# AnalogInputs.net
KiCad netlist of a schematic drawn in Altium Designer
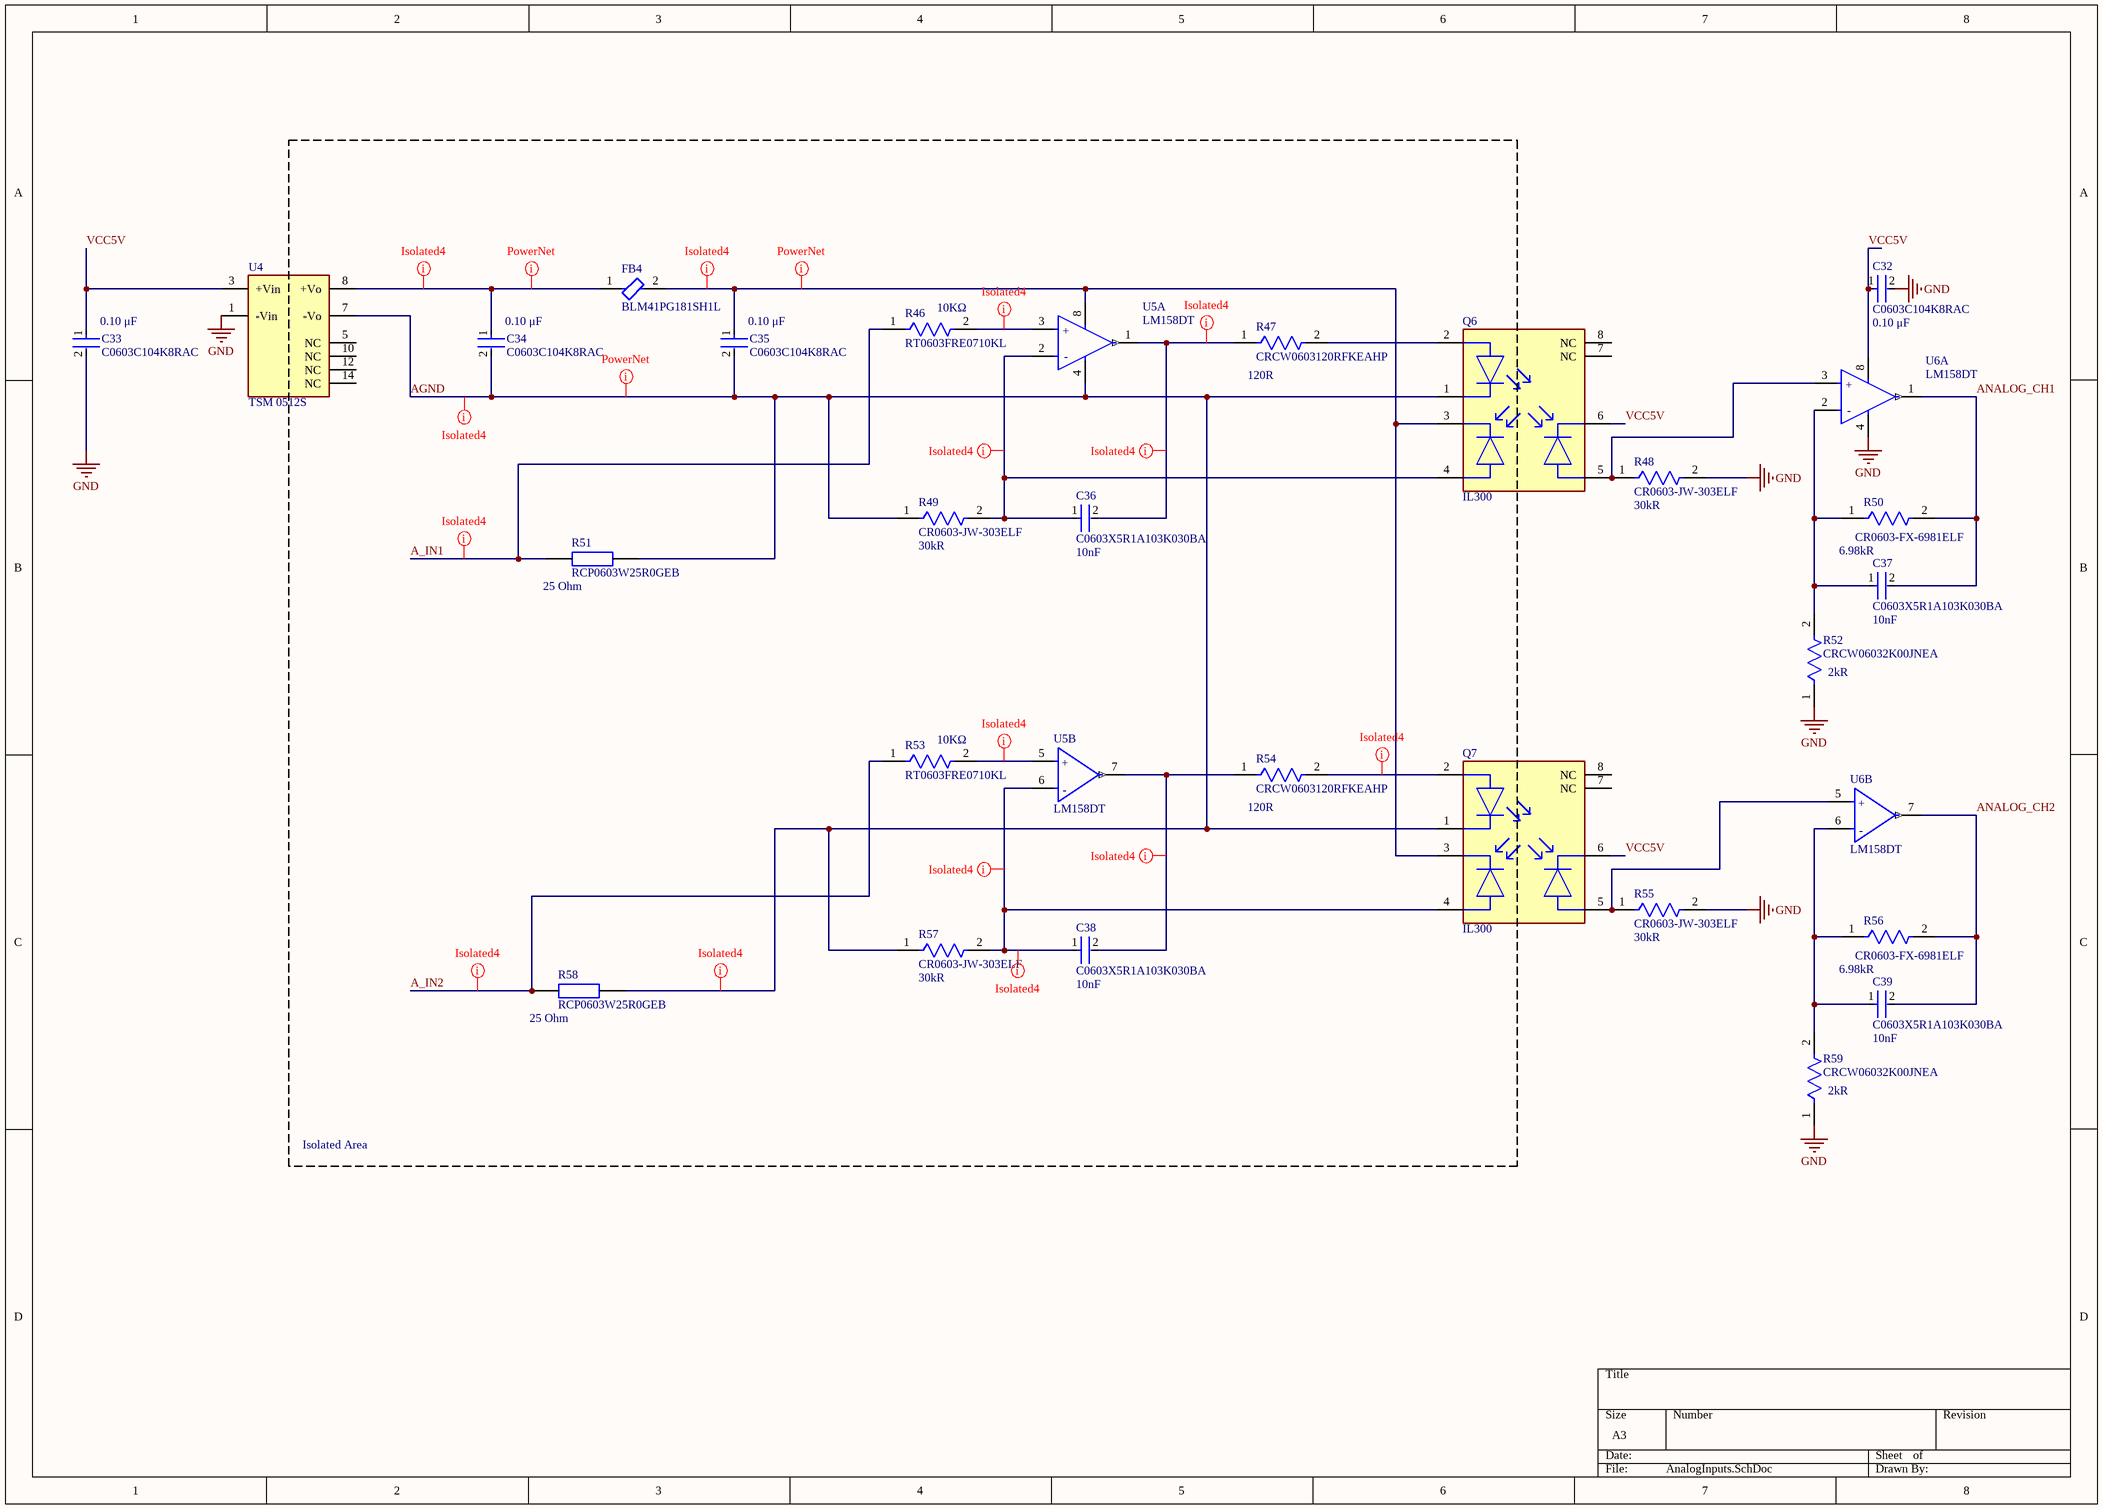
[diagram p0: AnalogInputs.SchDoc]

(export (version "E")
  (design (tool "Eeschema 10.0.6"))
  (components
    (comp (ref "C32")
      (value "C0603C104K8RAC")
      (footprint "FP-C0603C-CF-MFG")
      (description "C0603 0.10 μF X7R 30ppm/°C 10.00% 10 V")
      (fields
        (field (name "MANUFACTURER") "KEMET")
        (field (name "CAPACITANCE") "0.10 μF")
        (field (name "OCTOPART") "https://octopart.com/c0603c104k8rac-kemet-1325403")
      )
      (libsource (lib "Altium Content Vault") (part "b4654b650e69147ec39a6b967a45e02"))
    )
    (comp (ref "C33")
      (value "C0603C104K8RAC")
      (footprint "FP-C0603C-CF-MFG")
      (description "C0603 0.10 μF X7R 30ppm/°C 10.00% 10 V")
      (fields
        (field (name "MANUFACTURER") "KEMET")
        (field (name "CAPACITANCE") "0.10 μF")
        (field (name "OCTOPART") "https://octopart.com/c0603c104k8rac-kemet-1325403")
      )
      (libsource (lib "Altium Content Vault") (part "b4654b650e69147ec39a6b967a45e02"))
    )
    (comp (ref "C34")
      (value "C0603C104K8RAC")
      (footprint "FP-C0603C-CF-MFG")
      (description "C0603 0.10 μF X7R 30ppm/°C 10.00% 10 V")
      (fields
        (field (name "MANUFACTURER") "KEMET")
        (field (name "CAPACITANCE") "0.10 μF")
        (field (name "OCTOPART") "https://octopart.com/c0603c104k8rac-kemet-1325403")
      )
      (libsource (lib "Altium Content Vault") (part "b4654b650e69147ec39a6b967a45e02"))
    )
    (comp (ref "C35")
      (value "C0603C104K8RAC")
      (footprint "FP-C0603C-CF-MFG")
      (description "C0603 0.10 μF X7R 30ppm/°C 10.00% 10 V")
      (fields
        (field (name "MANUFACTURER") "KEMET")
        (field (name "CAPACITANCE") "0.10 μF")
        (field (name "OCTOPART") "https://octopart.com/c0603c104k8rac-kemet-1325403")
      )
      (libsource (lib "Altium Content Vault") (part "b4654b650e69147ec39a6b967a45e02"))
    )
    (comp (ref "C36")
      (value "C0603X5R1A103K030BA")
      (footprint "FP-C0603-030-0_03-MFG")
      (description "Multilayer Ceramic Capacitors 10nF ±10% 10V X5R SMD 0201")
      (fields
        (field (name "CAPACITANCE") "10nF")
        (field (name "TOLERANCE") "10%")
        (field (name "VOLTAGE") "10V")
      )
      (libsource (lib "Altium Content Vault") (part "02cd4be3c70576c341d710602a673aa"))
    )
    (comp (ref "C37")
      (value "C0603X5R1A103K030BA")
      (footprint "FP-C0603-030-0_03-MFG")
      (description "Multilayer Ceramic Capacitors 10nF ±10% 10V X5R SMD 0201")
      (fields
        (field (name "CAPACITANCE") "10nF")
        (field (name "TOLERANCE") "10%")
        (field (name "VOLTAGE") "10V")
      )
      (libsource (lib "Altium Content Vault") (part "02cd4be3c70576c341d710602a673aa"))
    )
    (comp (ref "C38")
      (value "C0603X5R1A103K030BA")
      (footprint "FP-C0603-030-0_03-MFG")
      (description "Multilayer Ceramic Capacitors 10nF ±10% 10V X5R SMD 0201")
      (fields
        (field (name "CAPACITANCE") "10nF")
        (field (name "TOLERANCE") "10%")
        (field (name "VOLTAGE") "10V")
      )
      (libsource (lib "Altium Content Vault") (part "02cd4be3c70576c341d710602a673aa"))
    )
    (comp (ref "C39")
      (value "C0603X5R1A103K030BA")
      (footprint "FP-C0603-030-0_03-MFG")
      (description "Multilayer Ceramic Capacitors 10nF ±10% 10V X5R SMD 0201")
      (fields
        (field (name "CAPACITANCE") "10nF")
        (field (name "TOLERANCE") "10%")
        (field (name "VOLTAGE") "10V")
      )
      (libsource (lib "Altium Content Vault") (part "02cd4be3c70576c341d710602a673aa"))
    )
    (comp (ref "FB4")
      (value "BLM41PG181SH1L")
      (footprint "FP-BLM41-0_2-a1_2-MFG")
      (description "Ferrite Bead, 1806, 180Ω @ 100MHz, 25%, 0.02Ω, 3.5A")
      (fields (field (name "TOLERANCE") "25%"))
      (libsource (lib "Altium Content Vault") (part "5f30dd21d616792df468990f7003faa"))
    )
    (comp (ref "Q6")
      (value "IL300")
      (footprint "FP-83265-MFG")
      (description "OPTOISO 5.3KV LINEAR PHVOLT 8DIP")
      (fields
        (field (name "OCTOPART") "https://octopart.com/il300-vishay-39692656")
        (field (name "MANUFACTURER") "Vishay")
      )
      (libsource (lib "Altium Content Vault") (part "7713484bad07440a39ee692e26a889a"))
    )
    (comp (ref "Q7")
      (value "IL300")
      (footprint "FP-83265-MFG")
      (description "OPTOISO 5.3KV LINEAR PHVOLT 8DIP")
      (fields
        (field (name "OCTOPART") "https://octopart.com/il300-vishay-39692656")
        (field (name "MANUFACTURER") "Vishay")
      )
      (libsource (lib "Altium Content Vault") (part "7713484bad07440a39ee692e26a889a"))
    )
    (comp (ref "R46")
      (value "RT0603FRE0710KL")
      (footprint "FP-RT0603-MFG")
      (description "RES SMD 10K OHM 1% 1/10W 0603")
      (fields
        (field (name "ALTIUM_VALUE") "10KΩ")
        (field (name "MANUFACTURER") "Yageo")
        (field (name "OCTOPART") "https://octopart.com/rt0603fre0710kl-yageo-40009243")
      )
      (libsource (lib "Altium Content Vault") (part "1029c3af85768c4190bb7ad29bc67b5"))
    )
    (comp (ref "R47")
      (value "CRCW0603120RFKEAHP")
      (footprint "FP-CRCW0603-HPe3-MFG")
      (description "RES Thick Film, 120Ω, 1%, 0.33W, 100ppm/°C, 0603")
      (fields (field (name "RESISTANCE") "120R") (field (name "TOLERANCE") "1%"))
      (libsource (lib "Altium Content Vault") (part "1029c3af85768c4190bb7ad29bc67b5"))
    )
    (comp (ref "R48")
      (value "CR0603-JW-303ELF")
      (footprint "FP-CR0603-MFG")
      (description "Thick Film Chip Resistors 0603 30kΩ 0.1W 5% 200ppm/°C")
      (fields (field (name "TOLERANCE") "5%") (field (name "RESISTANCE") "30kR"))
      (libsource (lib "Altium Content Vault") (part "1029c3af85768c4190bb7ad29bc67b5"))
    )
    (comp (ref "R49")
      (value "CR0603-JW-303ELF")
      (footprint "FP-CR0603-MFG")
      (description "Thick Film Chip Resistors 0603 30kΩ 0.1W 5% 200ppm/°C")
      (fields (field (name "TOLERANCE") "5%") (field (name "RESISTANCE") "30kR"))
      (libsource (lib "Altium Content Vault") (part "1029c3af85768c4190bb7ad29bc67b5"))
    )
    (comp (ref "R50")
      (value "CR0603-FX-6981ELF")
      (footprint "FP-CR0603-IPC_B")
      (description "Thick Film Chip Resistors 0603 6.98kΩ 0.1W 1% 100ppm/°C")
      (fields (field (name "RESISTANCE") "6.98kR") (field (name "TOLERANCE") "1%"))
      (libsource (lib "Altium Content Vault") (part "1029c3af85768c4190bb7ad29bc67b5"))
    )
    (comp (ref "R51")
      (value "RCP0603W25R0GEB")
      (footprint "RESC1608X59N")
      (description "Vishay 25 0603 (1608M) Thick Film SMD Resistor +/-2% 1.5W - RCP0603W25R0GEB")
      (fields (field (name "RESISTANCE") "25 Ohm"))
      (libsource (lib "Schlib2") (part "RCP0603W25R0GEB"))
    )
    (comp (ref "R52")
      (value "CRCW06032K00JNEA")
      (footprint "FP-CRCW0603-e3-MFG")
      (description "RES Thick Film, 2kΩ, 5%, 0.1W, 200ppm/°C, 0603")
      (fields (field (name "TOLERANCE") "5%") (field (name "RESISTANCE") "2kR"))
      (libsource (lib "Altium Content Vault") (part "1029c3af85768c4190bb7ad29bc67b5"))
    )
    (comp (ref "R53")
      (value "RT0603FRE0710KL")
      (footprint "FP-RT0603-MFG")
      (description "RES SMD 10K OHM 1% 1/10W 0603")
      (fields
        (field (name "ALTIUM_VALUE") "10KΩ")
        (field (name "MANUFACTURER") "Yageo")
        (field (name "OCTOPART") "https://octopart.com/rt0603fre0710kl-yageo-40009243")
      )
      (libsource (lib "Altium Content Vault") (part "1029c3af85768c4190bb7ad29bc67b5"))
    )
    (comp (ref "R54")
      (value "CRCW0603120RFKEAHP")
      (footprint "FP-CRCW0603-HPe3-MFG")
      (description "RES Thick Film, 120Ω, 1%, 0.33W, 100ppm/°C, 0603")
      (fields (field (name "RESISTANCE") "120R") (field (name "TOLERANCE") "1%"))
      (libsource (lib "Altium Content Vault") (part "1029c3af85768c4190bb7ad29bc67b5"))
    )
    (comp (ref "R55")
      (value "CR0603-JW-303ELF")
      (footprint "FP-CR0603-MFG")
      (description "Thick Film Chip Resistors 0603 30kΩ 0.1W 5% 200ppm/°C")
      (fields (field (name "TOLERANCE") "5%") (field (name "RESISTANCE") "30kR"))
      (libsource (lib "Altium Content Vault") (part "1029c3af85768c4190bb7ad29bc67b5"))
    )
    (comp (ref "R56")
      (value "CR0603-FX-6981ELF")
      (footprint "FP-CR0603-IPC_B")
      (description "Thick Film Chip Resistors 0603 6.98kΩ 0.1W 1% 100ppm/°C")
      (fields (field (name "RESISTANCE") "6.98kR") (field (name "TOLERANCE") "1%"))
      (libsource (lib "Altium Content Vault") (part "1029c3af85768c4190bb7ad29bc67b5"))
    )
    (comp (ref "R57")
      (value "CR0603-JW-303ELF")
      (footprint "FP-CR0603-MFG")
      (description "Thick Film Chip Resistors 0603 30kΩ 0.1W 5% 200ppm/°C")
      (fields (field (name "TOLERANCE") "5%") (field (name "RESISTANCE") "30kR"))
      (libsource (lib "Altium Content Vault") (part "1029c3af85768c4190bb7ad29bc67b5"))
    )
    (comp (ref "R58")
      (value "RCP0603W25R0GEB")
      (footprint "RESC1608X59N")
      (description "Vishay 25 0603 (1608M) Thick Film SMD Resistor +/-2% 1.5W - RCP0603W25R0GEB")
      (fields (field (name "RESISTANCE") "25 Ohm"))
      (libsource (lib "Schlib2") (part "RCP0603W25R0GEB"))
    )
    (comp (ref "R59")
      (value "CRCW06032K00JNEA")
      (footprint "FP-CRCW0603-e3-MFG")
      (description "RES Thick Film, 2kΩ, 5%, 0.1W, 200ppm/°C, 0603")
      (fields (field (name "TOLERANCE") "5%") (field (name "RESISTANCE") "2kR"))
      (libsource (lib "Altium Content Vault") (part "1029c3af85768c4190bb7ad29bc67b5"))
    )
    (comp (ref "U4")
      (value "TSM 0512S")
      (footprint "FP-TSM_0512S-MFG")
      (description "DC DC CONVERTER 12V 960MW")
      (fields
        (field (name "OCTOPART") "https://octopart.com/tsm+0512s-tracopower-7394392")
        (field (name "MANUFACTURER") "Tracopower")
      )
      (libsource (lib "Altium Content Vault") (part "eabb76d147af65372c0c780fc4b7452"))
    )
    (comp (ref "U5")
      (value "LM158DT")
      (footprint "FP-SO8-IPC_C")
      (description "IC OPAMP GP 2 CIRCUIT 8SO")
      (fields
        (field (name "MANUFACTURER") "STMicroelectronics")
        (field (name "OCTOPART") "https://octopart.com/lm158dt-stmicroelectronics-11026426")
      )
      (libsource (lib "Altium Content Vault") (part "5d7e14b575c37a4dd5fc6126976b1ba"))
    )
    (comp (ref "U6")
      (value "LM158DT")
      (footprint "FP-SO8-IPC_C")
      (description "IC OPAMP GP 2 CIRCUIT 8SO")
      (fields
        (field (name "MANUFACTURER") "STMicroelectronics")
        (field (name "OCTOPART") "https://octopart.com/lm158dt-stmicroelectronics-11026426")
      )
      (libsource (lib "Altium Content Vault") (part "5d7e14b575c37a4dd5fc6126976b1ba"))
    )
  )
  (nets
    (net (code "1") (name "/AGND") (class "Default")
      (node (ref "C34") (pin "2") (pinfunction "2_2") (pintype "passive"))
      (node (ref "C35") (pin "2") (pinfunction "2_2") (pintype "passive"))
      (node (ref "Q6") (pin "1") (pinfunction "1_CATHODE_1") (pintype "passive"))
      (node (ref "Q7") (pin "1") (pinfunction "1_CATHODE_1") (pintype "passive"))
      (node (ref "R49") (pin "1") (pinfunction "1_1") (pintype "passive"))
      (node (ref "R51") (pin "2") (pinfunction "2_2") (pintype "passive"))
      (node (ref "R57") (pin "1") (pinfunction "1_1") (pintype "passive"))
      (node (ref "R58") (pin "2") (pinfunction "2_2") (pintype "passive"))
      (node (ref "U4") (pin "7") (pinfunction "-Vo_7") (pintype "power_in"))
      (node (ref "U5") (pin "4") (pinfunction "Vcc-_4") (pintype "power_in"))
    )
    (net (code "2") (name "/ANALOG_CH1") (class "Default")
      (node (ref "C37") (pin "2") (pinfunction "2_2") (pintype "passive"))
      (node (ref "R50") (pin "2") (pinfunction "2_2") (pintype "passive"))
      (node (ref "U6") (pin "1") (pinfunction "Out1_1") (pintype "output"))
    )
    (net (code "3") (name "/ANALOG_CH2") (class "Default")
      (node (ref "C39") (pin "2") (pinfunction "2_2") (pintype "passive"))
      (node (ref "R56") (pin "2") (pinfunction "2_2") (pintype "passive"))
      (node (ref "U6") (pin "7") (pinfunction "Out2_7") (pintype "output"))
    )
    (net (code "4") (name "/A_IN1") (class "Default")
      (node (ref "R46") (pin "1") (pinfunction "1_1") (pintype "passive"))
      (node (ref "R51") (pin "1") (pinfunction "1_1") (pintype "passive"))
    )
    (net (code "5") (name "/A_IN2") (class "Default")
      (node (ref "R53") (pin "1") (pinfunction "1_1") (pintype "passive"))
      (node (ref "R58") (pin "1") (pinfunction "1_1") (pintype "passive"))
    )
    (net (code "6") (name "/VCC5V") (class "Default")
      (node (ref "C32") (pin "1") (pinfunction "1_1") (pintype "passive"))
      (node (ref "C33") (pin "1") (pinfunction "1_1") (pintype "passive"))
      (node (ref "Q6") (pin "6") (pinfunction "3_CATHODE_6") (pintype "passive"))
      (node (ref "Q7") (pin "6") (pinfunction "3_CATHODE_6") (pintype "passive"))
      (node (ref "U4") (pin "3") (pinfunction "+Vin_3") (pintype "power_in"))
      (node (ref "U6") (pin "8") (pinfunction "Vcc+_8") (pintype "power_in"))
    )
    (net (code "7") (name "GND") (class "Default")
      (node (ref "C32") (pin "2") (pinfunction "2_2") (pintype "passive"))
      (node (ref "C33") (pin "2") (pinfunction "2_2") (pintype "passive"))
      (node (ref "R48") (pin "2") (pinfunction "2_2") (pintype "passive"))
      (node (ref "R52") (pin "1") (pinfunction "1_1") (pintype "passive"))
      (node (ref "R55") (pin "2") (pinfunction "2_2") (pintype "passive"))
      (node (ref "R59") (pin "1") (pinfunction "1_1") (pintype "passive"))
      (node (ref "U4") (pin "1") (pinfunction "-Vin_1") (pintype "power_in"))
      (node (ref "U6") (pin "4") (pinfunction "Vcc-_4") (pintype "power_in"))
    )
    (net (code "8") (name "Net-(Q6-1_ANODE)") (class "Default")
      (node (ref "Q6") (pin "2") (pinfunction "1_ANODE_2") (pintype "passive"))
      (node (ref "R47") (pin "2") (pinfunction "2_2") (pintype "passive"))
    )
    (net (code "9") (name "Net-(Q6-2_ANODE)") (class "Default")
      (node (ref "C36") (pin "1") (pinfunction "1_1") (pintype "passive"))
      (node (ref "Q6") (pin "4") (pinfunction "2_ANODE_4") (pintype "passive"))
      (node (ref "R49") (pin "2") (pinfunction "2_2") (pintype "passive"))
      (node (ref "U5") (pin "2") (pinfunction "In1-_2") (pintype "tri_state"))
    )
    (net (code "10") (name "Net-(Q6-2_CATHODE)") (class "Default")
      (node (ref "C35") (pin "1") (pinfunction "1_1") (pintype "passive"))
      (node (ref "FB4") (pin "2") (pinfunction "2_2") (pintype "passive"))
      (node (ref "Q6") (pin "3") (pinfunction "2_CATHODE_3") (pintype "passive"))
      (node (ref "Q7") (pin "3") (pinfunction "2_CATHODE_3") (pintype "passive"))
      (node (ref "U5") (pin "8") (pinfunction "Vcc+_8") (pintype "power_in"))
    )
    (net (code "11") (name "Net-(Q6-3_ANODE)") (class "Default")
      (node (ref "Q6") (pin "5") (pinfunction "3_ANODE_5") (pintype "passive"))
      (node (ref "R48") (pin "1") (pinfunction "1_1") (pintype "passive"))
      (node (ref "U6") (pin "3") (pinfunction "In1+_3") (pintype "tri_state"))
    )
    (net (code "12") (name "Net-(Q7-1_ANODE)") (class "Default")
      (node (ref "Q7") (pin "2") (pinfunction "1_ANODE_2") (pintype "passive"))
      (node (ref "R54") (pin "2") (pinfunction "2_2") (pintype "passive"))
    )
    (net (code "13") (name "Net-(Q7-2_ANODE)") (class "Default")
      (node (ref "C38") (pin "1") (pinfunction "1_1") (pintype "passive"))
      (node (ref "Q7") (pin "4") (pinfunction "2_ANODE_4") (pintype "passive"))
      (node (ref "R57") (pin "2") (pinfunction "2_2") (pintype "passive"))
      (node (ref "U5") (pin "6") (pinfunction "In2-_6") (pintype "tri_state"))
    )
    (net (code "14") (name "Net-(Q7-3_ANODE)") (class "Default")
      (node (ref "Q7") (pin "5") (pinfunction "3_ANODE_5") (pintype "passive"))
      (node (ref "R55") (pin "1") (pinfunction "1_1") (pintype "passive"))
      (node (ref "U6") (pin "5") (pinfunction "In2+_5") (pintype "tri_state"))
    )
    (net (code "15") (name "Net-(U4-+Vo)") (class "Default")
      (node (ref "C34") (pin "1") (pinfunction "1_1") (pintype "passive"))
      (node (ref "FB4") (pin "1") (pinfunction "1_1") (pintype "passive"))
      (node (ref "U4") (pin "8") (pinfunction "+Vo_8") (pintype "power_in"))
    )
    (net (code "16") (name "Net-(U5A-In1+)") (class "Default")
      (node (ref "R46") (pin "2") (pinfunction "2_2") (pintype "passive"))
      (node (ref "U5") (pin "3") (pinfunction "In1+_3") (pintype "tri_state"))
    )
    (net (code "17") (name "Net-(U5A-Out1)") (class "Default")
      (node (ref "C36") (pin "2") (pinfunction "2_2") (pintype "passive"))
      (node (ref "R47") (pin "1") (pinfunction "1_1") (pintype "passive"))
      (node (ref "U5") (pin "1") (pinfunction "Out1_1") (pintype "output"))
    )
    (net (code "18") (name "Net-(U5B-In2+)") (class "Default")
      (node (ref "R53") (pin "2") (pinfunction "2_2") (pintype "passive"))
      (node (ref "U5") (pin "5") (pinfunction "In2+_5") (pintype "tri_state"))
    )
    (net (code "19") (name "Net-(U5B-Out2)") (class "Default")
      (node (ref "C38") (pin "2") (pinfunction "2_2") (pintype "passive"))
      (node (ref "R54") (pin "1") (pinfunction "1_1") (pintype "passive"))
      (node (ref "U5") (pin "7") (pinfunction "Out2_7") (pintype "output"))
    )
    (net (code "20") (name "Net-(U6A-In1-)") (class "Default")
      (node (ref "C37") (pin "1") (pinfunction "1_1") (pintype "passive"))
      (node (ref "R50") (pin "1") (pinfunction "1_1") (pintype "passive"))
      (node (ref "R52") (pin "2") (pinfunction "2_2") (pintype "passive"))
      (node (ref "U6") (pin "2") (pinfunction "In1-_2") (pintype "tri_state"))
    )
    (net (code "21") (name "Net-(U6B-In2-)") (class "Default")
      (node (ref "C39") (pin "1") (pinfunction "1_1") (pintype "passive"))
      (node (ref "R56") (pin "1") (pinfunction "1_1") (pintype "passive"))
      (node (ref "R59") (pin "2") (pinfunction "2_2") (pintype "passive"))
      (node (ref "U6") (pin "6") (pinfunction "In2-_6") (pintype "tri_state"))
    )
    (net (code "22") (name "unconnected-(Q6-NC-Pad7)") (class "Default")
      (node (ref "Q6") (pin "7") (pinfunction "NC_7") (pintype "passive"))
    )
    (net (code "23") (name "unconnected-(Q6-NC-Pad8)") (class "Default")
      (node (ref "Q6") (pin "8") (pinfunction "NC_8") (pintype "passive"))
    )
    (net (code "24") (name "unconnected-(Q7-NC-Pad7)") (class "Default")
      (node (ref "Q7") (pin "7") (pinfunction "NC_7") (pintype "passive"))
    )
    (net (code "25") (name "unconnected-(Q7-NC-Pad8)") (class "Default")
      (node (ref "Q7") (pin "8") (pinfunction "NC_8") (pintype "passive"))
    )
    (net (code "26") (name "unconnected-(U4-NC-Pad5)") (class "Default")
      (node (ref "U4") (pin "5") (pinfunction "NC_5") (pintype "passive"))
    )
    (net (code "27") (name "unconnected-(U4-NC-Pad10)") (class "Default")
      (node (ref "U4") (pin "10") (pinfunction "NC_10") (pintype "passive"))
    )
    (net (code "28") (name "unconnected-(U4-NC-Pad12)") (class "Default")
      (node (ref "U4") (pin "12") (pinfunction "NC_12") (pintype "passive"))
    )
    (net (code "29") (name "unconnected-(U4-NC-Pad14)") (class "Default")
      (node (ref "U4") (pin "14") (pinfunction "NC_14") (pintype "passive"))
    )
  )
)
